# ders1.net
KiCad netlist of a schematic drawn in EAGLE
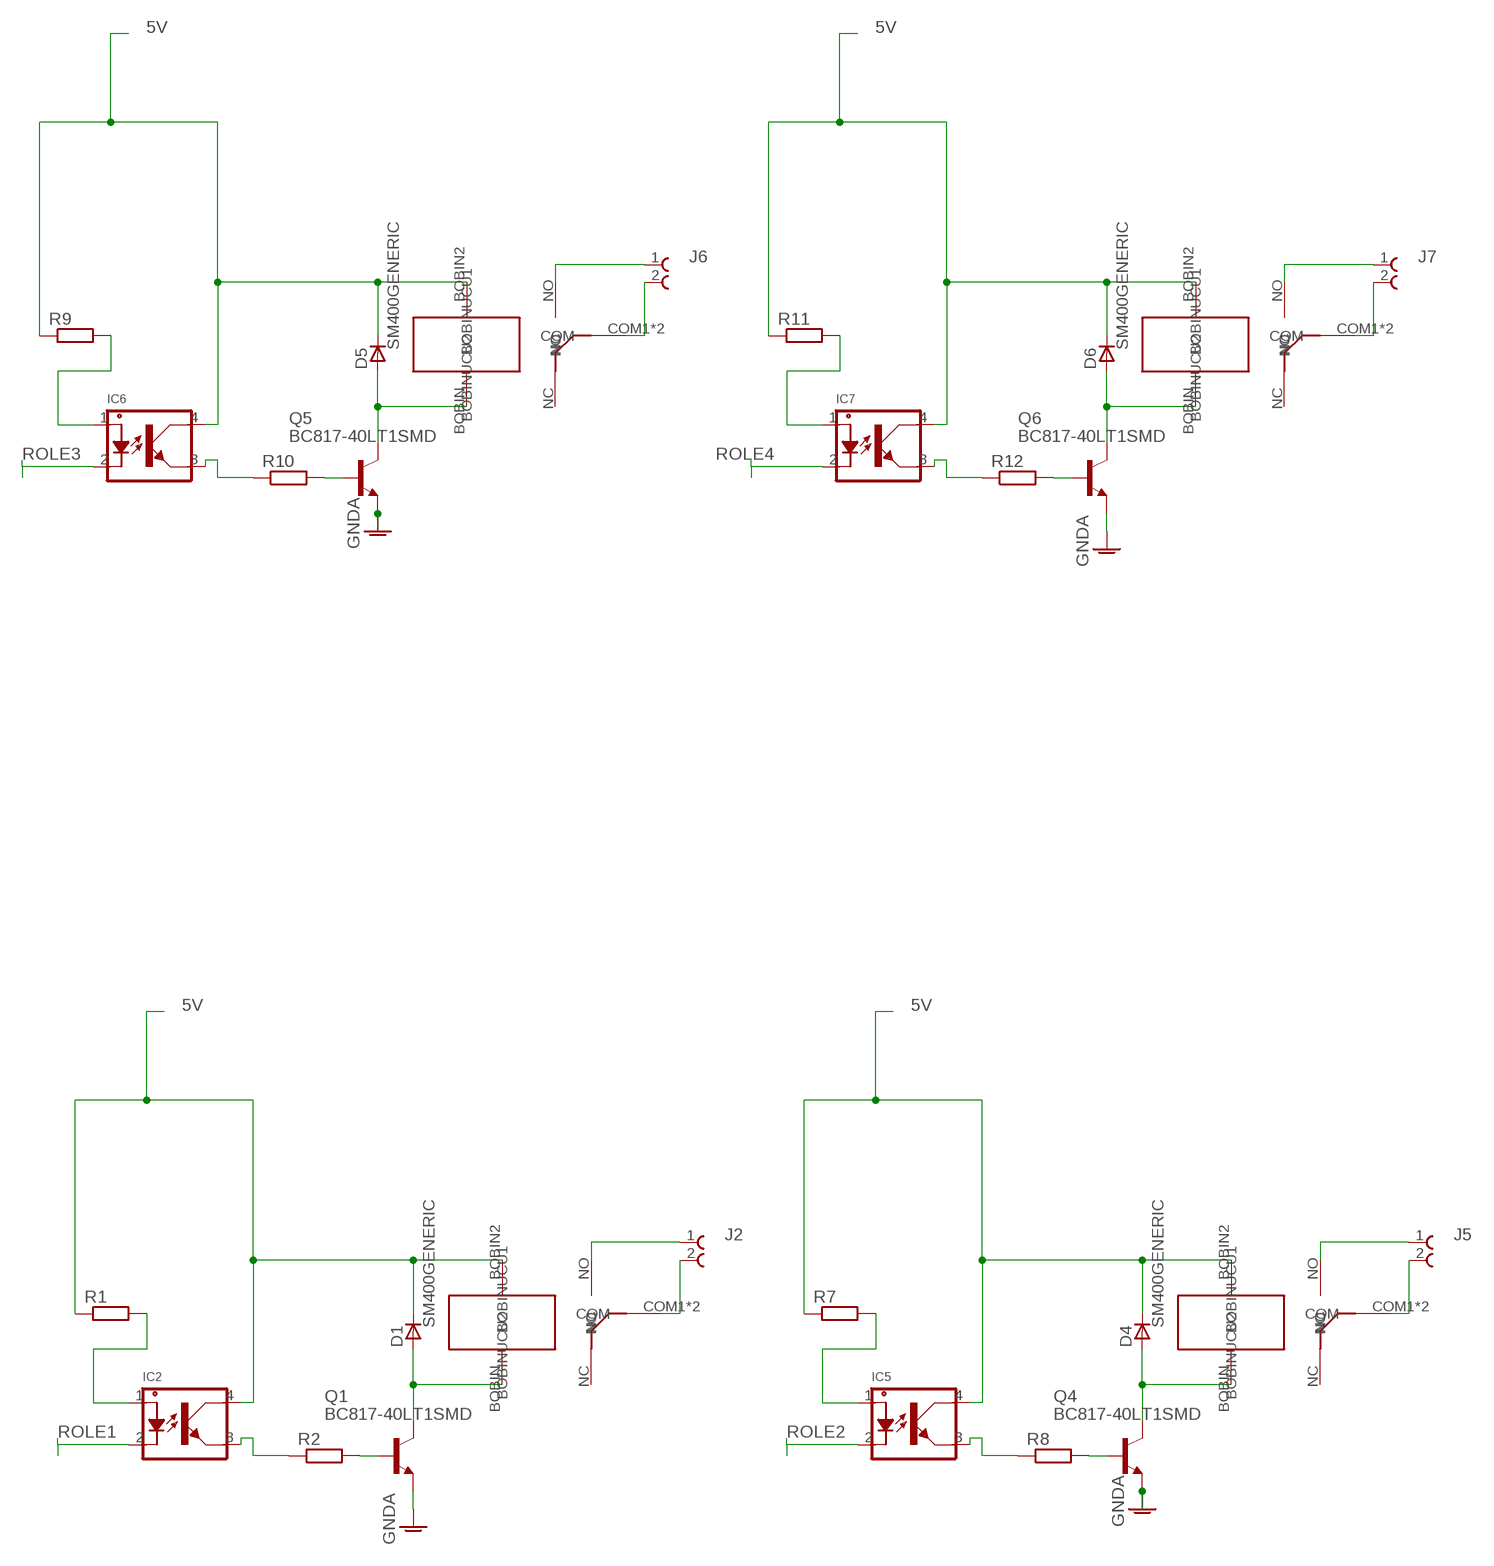
[diagram p0: schematic, sheet 1, part 1 of 2]
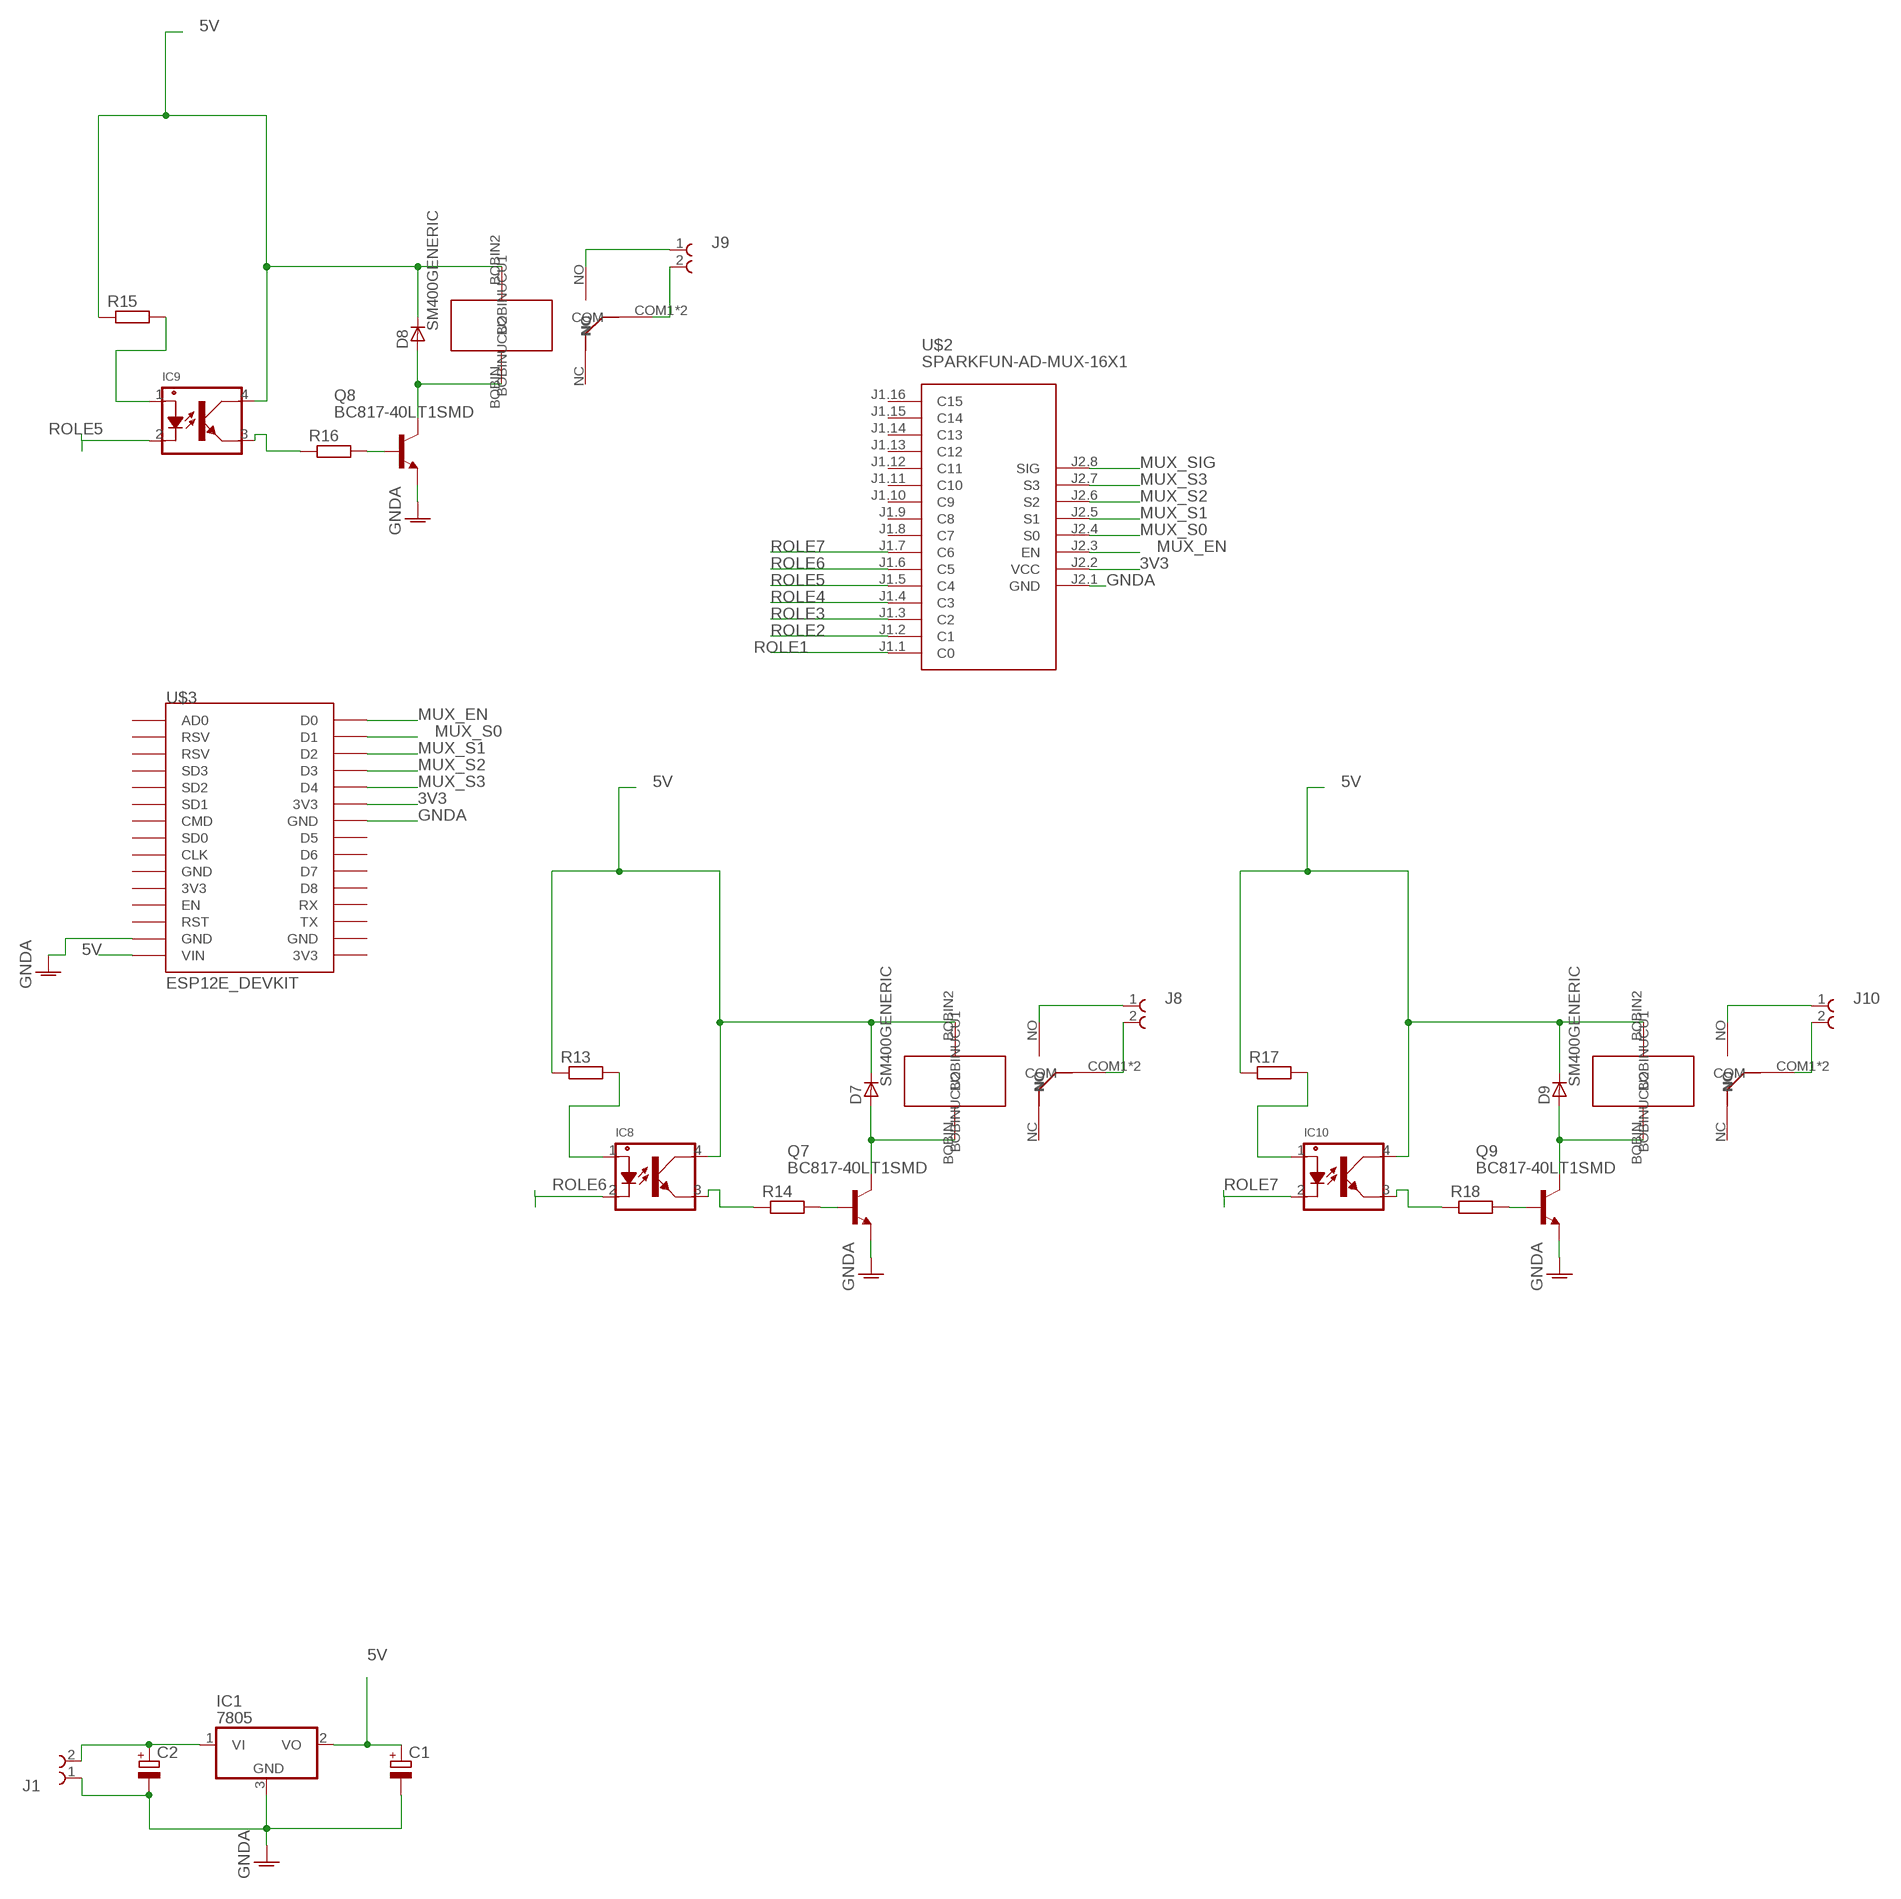
[diagram p1: schematic, sheet 1, part 2 of 2]

(export (version "E")
  (design (tool "Eeschema 10.0.6"))
  (components
    (comp (ref "C1")
      (value "CPOL-EU153CLV-0405")
      (footprint "eagle-import:153CLV-0405")
      (libsource (lib "eagle-import") (part "CPOL-EU153CLV-0405"))
    )
    (comp (ref "C2")
      (value "CPOL-EU153CLV-0405")
      (footprint "eagle-import:153CLV-0405")
      (libsource (lib "eagle-import") (part "CPOL-EU153CLV-0405"))
    )
    (comp (ref "D1")
      (value "SM400GENERIC")
      (footprint "eagle-import:MELF-MLL41_DO213AB")
      (libsource (lib "eagle-import") (part "SM400GENERIC"))
    )
    (comp (ref "D4")
      (value "SM400GENERIC")
      (footprint "eagle-import:MELF-MLL41_DO213AB")
      (libsource (lib "eagle-import") (part "SM400GENERIC"))
    )
    (comp (ref "D5")
      (value "SM400GENERIC")
      (footprint "eagle-import:MELF-MLL41_DO213AB")
      (libsource (lib "eagle-import") (part "SM400GENERIC"))
    )
    (comp (ref "D6")
      (value "SM400GENERIC")
      (footprint "eagle-import:MELF-MLL41_DO213AB")
      (libsource (lib "eagle-import") (part "SM400GENERIC"))
    )
    (comp (ref "D7")
      (value "SM400GENERIC")
      (footprint "eagle-import:MELF-MLL41_DO213AB")
      (libsource (lib "eagle-import") (part "SM400GENERIC"))
    )
    (comp (ref "D8")
      (value "SM400GENERIC")
      (footprint "eagle-import:MELF-MLL41_DO213AB")
      (libsource (lib "eagle-import") (part "SM400GENERIC"))
    )
    (comp (ref "D9")
      (value "SM400GENERIC")
      (footprint "eagle-import:MELF-MLL41_DO213AB")
      (libsource (lib "eagle-import") (part "SM400GENERIC"))
    )
    (comp (ref "IC1")
      (value "7805")
      (footprint "eagle-import:TO252")
      (libsource (lib "eagle-import") (part "7805"))
    )
    (comp (ref "IC2")
      (value "LTV-817SMD")
      (footprint "eagle-import:SMD-4")
      (fields (field (name "MF") "Lite-On Inc.") (field (name "MP") "LTV-817"))
      (libsource (lib "eagle-import") (part "LTV-817SMD"))
    )
    (comp (ref "IC5")
      (value "LTV-817SMD")
      (footprint "eagle-import:SMD-4")
      (fields (field (name "MF") "Lite-On Inc.") (field (name "MP") "LTV-817"))
      (libsource (lib "eagle-import") (part "LTV-817SMD"))
    )
    (comp (ref "IC6")
      (value "LTV-817SMD")
      (footprint "eagle-import:SMD-4")
      (fields (field (name "MF") "Lite-On Inc.") (field (name "MP") "LTV-817"))
      (libsource (lib "eagle-import") (part "LTV-817SMD"))
    )
    (comp (ref "IC7")
      (value "LTV-817SMD")
      (footprint "eagle-import:SMD-4")
      (fields (field (name "MF") "Lite-On Inc.") (field (name "MP") "LTV-817"))
      (libsource (lib "eagle-import") (part "LTV-817SMD"))
    )
    (comp (ref "IC8")
      (value "LTV-817SMD")
      (footprint "eagle-import:SMD-4")
      (fields (field (name "MF") "Lite-On Inc.") (field (name "MP") "LTV-817"))
      (libsource (lib "eagle-import") (part "LTV-817SMD"))
    )
    (comp (ref "IC9")
      (value "LTV-817SMD")
      (footprint "eagle-import:SMD-4")
      (fields (field (name "MF") "Lite-On Inc.") (field (name "MP") "LTV-817"))
      (libsource (lib "eagle-import") (part "LTV-817SMD"))
    )
    (comp (ref "IC10")
      (value "LTV-817SMD")
      (footprint "eagle-import:SMD-4")
      (fields (field (name "MF") "Lite-On Inc.") (field (name "MP") "LTV-817"))
      (libsource (lib "eagle-import") (part "LTV-817SMD"))
    )
    (comp (ref "J1")
      (value "691701540002B")
      (footprint "eagle-import:691701540002B")
      (libsource (lib "eagle-import") (part "691701540002B"))
    )
    (comp (ref "J2")
      (value "691701540002B")
      (footprint "eagle-import:691701540002B")
      (libsource (lib "eagle-import") (part "691701540002B"))
    )
    (comp (ref "J5")
      (value "691701540002B")
      (footprint "eagle-import:691701540002B")
      (libsource (lib "eagle-import") (part "691701540002B"))
    )
    (comp (ref "J6")
      (value "691701540002B")
      (footprint "eagle-import:691701540002B")
      (libsource (lib "eagle-import") (part "691701540002B"))
    )
    (comp (ref "J7")
      (value "691701540002B")
      (footprint "eagle-import:691701540002B")
      (libsource (lib "eagle-import") (part "691701540002B"))
    )
    (comp (ref "J8")
      (value "691701540002B")
      (footprint "eagle-import:691701540002B")
      (libsource (lib "eagle-import") (part "691701540002B"))
    )
    (comp (ref "J9")
      (value "691701540002B")
      (footprint "eagle-import:691701540002B")
      (libsource (lib "eagle-import") (part "691701540002B"))
    )
    (comp (ref "J10")
      (value "691701540002B")
      (footprint "eagle-import:691701540002B")
      (libsource (lib "eagle-import") (part "691701540002B"))
    )
    (comp (ref "Q1")
      (value "BC817-40LT1SMD")
      (footprint "eagle-import:SOT23-BEC")
      (libsource (lib "eagle-import") (part "BC817SMD-40LT1"))
    )
    (comp (ref "Q4")
      (value "BC817-40LT1SMD")
      (footprint "eagle-import:SOT23-BEC")
      (libsource (lib "eagle-import") (part "BC817SMD-40LT1"))
    )
    (comp (ref "Q5")
      (value "BC817-40LT1SMD")
      (footprint "eagle-import:SOT23-BEC")
      (libsource (lib "eagle-import") (part "BC817SMD-40LT1"))
    )
    (comp (ref "Q6")
      (value "BC817-40LT1SMD")
      (footprint "eagle-import:SOT23-BEC")
      (libsource (lib "eagle-import") (part "BC817SMD-40LT1"))
    )
    (comp (ref "Q7")
      (value "BC817-40LT1SMD")
      (footprint "eagle-import:SOT23-BEC")
      (libsource (lib "eagle-import") (part "BC817SMD-40LT1"))
    )
    (comp (ref "Q8")
      (value "BC817-40LT1SMD")
      (footprint "eagle-import:SOT23-BEC")
      (libsource (lib "eagle-import") (part "BC817SMD-40LT1"))
    )
    (comp (ref "Q9")
      (value "BC817-40LT1SMD")
      (footprint "eagle-import:SOT23-BEC")
      (libsource (lib "eagle-import") (part "BC817SMD-40LT1"))
    )
    (comp (ref "R1")
      (value "R-EU_R1206")
      (footprint "eagle-import:R1206")
      (libsource (lib "eagle-import") (part "R-EU_R1206"))
    )
    (comp (ref "R2")
      (value "R-EU_R1206")
      (footprint "eagle-import:R1206")
      (libsource (lib "eagle-import") (part "R-EU_R1206"))
    )
    (comp (ref "R7")
      (value "R-EU_R1206")
      (footprint "eagle-import:R1206")
      (libsource (lib "eagle-import") (part "R-EU_R1206"))
    )
    (comp (ref "R8")
      (value "R-EU_R1206")
      (footprint "eagle-import:R1206")
      (libsource (lib "eagle-import") (part "R-EU_R1206"))
    )
    (comp (ref "R9")
      (value "R-EU_R1206")
      (footprint "eagle-import:R1206")
      (libsource (lib "eagle-import") (part "R-EU_R1206"))
    )
    (comp (ref "R10")
      (value "R-EU_R1206")
      (footprint "eagle-import:R1206")
      (libsource (lib "eagle-import") (part "R-EU_R1206"))
    )
    (comp (ref "R11")
      (value "R-EU_R1206")
      (footprint "eagle-import:R1206")
      (libsource (lib "eagle-import") (part "R-EU_R1206"))
    )
    (comp (ref "R12")
      (value "R-EU_R1206")
      (footprint "eagle-import:R1206")
      (libsource (lib "eagle-import") (part "R-EU_R1206"))
    )
    (comp (ref "R13")
      (value "R-EU_R1206")
      (footprint "eagle-import:R1206")
      (libsource (lib "eagle-import") (part "R-EU_R1206"))
    )
    (comp (ref "R14")
      (value "R-EU_R1206")
      (footprint "eagle-import:R1206")
      (libsource (lib "eagle-import") (part "R-EU_R1206"))
    )
    (comp (ref "R15")
      (value "R-EU_R1206")
      (footprint "eagle-import:R1206")
      (libsource (lib "eagle-import") (part "R-EU_R1206"))
    )
    (comp (ref "R16")
      (value "R-EU_R1206")
      (footprint "eagle-import:R1206")
      (libsource (lib "eagle-import") (part "R-EU_R1206"))
    )
    (comp (ref "R17")
      (value "R-EU_R1206")
      (footprint "eagle-import:R1206")
      (libsource (lib "eagle-import") (part "R-EU_R1206"))
    )
    (comp (ref "R18")
      (value "R-EU_R1206")
      (footprint "eagle-import:R1206")
      (libsource (lib "eagle-import") (part "R-EU_R1206"))
    )
    (comp (ref "U$1")
      (value "HK23F-DC5V-SHG")
      (footprint "eagle-import:HK23F")
      (libsource (lib "eagle-import") (part "HK23F-DC5V-SHG"))
    )
    (comp (ref "U$2")
      (value "SPARKFUN-AD-MUX-16X1")
      (footprint "eagle-import:SPARKFUN-AD-MUX-16X1")
      (libsource (lib "eagle-import") (part "SPARKFUN-AD-MUX-16X1"))
    )
    (comp (ref "U$3")
      (value "ESP12E_DEVKIT")
      (footprint "eagle-import:ESP12E_DEVKIT")
      (libsource (lib "eagle-import") (part "ESP12E_DEVKIT"))
    )
    (comp (ref "U$4")
      (value "HK23F-DC5V-SHG")
      (footprint "eagle-import:HK23F")
      (libsource (lib "eagle-import") (part "HK23F-DC5V-SHG"))
    )
    (comp (ref "U$5")
      (value "HK23F-DC5V-SHG")
      (footprint "eagle-import:HK23F")
      (libsource (lib "eagle-import") (part "HK23F-DC5V-SHG"))
    )
    (comp (ref "U$6")
      (value "HK23F-DC5V-SHG")
      (footprint "eagle-import:HK23F")
      (libsource (lib "eagle-import") (part "HK23F-DC5V-SHG"))
    )
    (comp (ref "U$7")
      (value "HK23F-DC5V-SHG")
      (footprint "eagle-import:HK23F")
      (libsource (lib "eagle-import") (part "HK23F-DC5V-SHG"))
    )
    (comp (ref "U$8")
      (value "HK23F-DC5V-SHG")
      (footprint "eagle-import:HK23F")
      (libsource (lib "eagle-import") (part "HK23F-DC5V-SHG"))
    )
    (comp (ref "U$9")
      (value "HK23F-DC5V-SHG")
      (footprint "eagle-import:HK23F")
      (libsource (lib "eagle-import") (part "HK23F-DC5V-SHG"))
    )
  )
  (nets
    (net (code "1") (name "/3V3") (class "Default")
      (node (ref "U$2") (pin "J2.2") (pinfunction "VCC_J2.2") (pintype "power_in"))
      (node (ref "U$3") (pin "3V3@1") (pinfunction "3V3_3V3@1") (pintype "bidirectional"))
    )
    (net (code "2") (name "/5V") (class "Default")
      (node (ref "C1") (pin "+") (pinfunction "+_+") (pintype "passive"))
      (node (ref "D1") (pin "C") (pinfunction "C_C") (pintype "passive"))
      (node (ref "D4") (pin "C") (pinfunction "C_C") (pintype "passive"))
      (node (ref "D5") (pin "C") (pinfunction "C_C") (pintype "passive"))
      (node (ref "D6") (pin "C") (pinfunction "C_C") (pintype "passive"))
      (node (ref "D7") (pin "C") (pinfunction "C_C") (pintype "passive"))
      (node (ref "D8") (pin "C") (pinfunction "C_C") (pintype "passive"))
      (node (ref "D9") (pin "C") (pinfunction "C_C") (pintype "passive"))
      (node (ref "IC1") (pin "2") (pinfunction "VO_2") (pintype "passive"))
      (node (ref "IC10") (pin "4") (pinfunction "4_4") (pintype "input"))
      (node (ref "IC2") (pin "4") (pinfunction "4_4") (pintype "input"))
      (node (ref "IC5") (pin "4") (pinfunction "4_4") (pintype "input"))
      (node (ref "IC6") (pin "4") (pinfunction "4_4") (pintype "input"))
      (node (ref "IC7") (pin "4") (pinfunction "4_4") (pintype "input"))
      (node (ref "IC8") (pin "4") (pinfunction "4_4") (pintype "input"))
      (node (ref "IC9") (pin "4") (pinfunction "4_4") (pintype "input"))
      (node (ref "R1") (pin "1") (pinfunction "1_1") (pintype "passive"))
      (node (ref "R11") (pin "1") (pinfunction "1_1") (pintype "passive"))
      (node (ref "R13") (pin "1") (pinfunction "1_1") (pintype "passive"))
      (node (ref "R15") (pin "1") (pinfunction "1_1") (pintype "passive"))
      (node (ref "R17") (pin "1") (pinfunction "1_1") (pintype "passive"))
      (node (ref "R7") (pin "1") (pinfunction "1_1") (pintype "passive"))
      (node (ref "R9") (pin "1") (pinfunction "1_1") (pintype "passive"))
      (node (ref "U$1") (pin "BOBIN2") (pinfunction "BOBINUCU2_BOBIN2") (pintype "bidirectional"))
      (node (ref "U$3") (pin "VIN") (pinfunction "VIN_VIN") (pintype "bidirectional"))
      (node (ref "U$4") (pin "BOBIN2") (pinfunction "BOBINUCU2_BOBIN2") (pintype "bidirectional"))
      (node (ref "U$5") (pin "BOBIN2") (pinfunction "BOBINUCU2_BOBIN2") (pintype "bidirectional"))
      (node (ref "U$6") (pin "BOBIN2") (pinfunction "BOBINUCU2_BOBIN2") (pintype "bidirectional"))
      (node (ref "U$7") (pin "BOBIN2") (pinfunction "BOBINUCU2_BOBIN2") (pintype "bidirectional"))
      (node (ref "U$8") (pin "BOBIN2") (pinfunction "BOBINUCU2_BOBIN2") (pintype "bidirectional"))
      (node (ref "U$9") (pin "BOBIN2") (pinfunction "BOBINUCU2_BOBIN2") (pintype "bidirectional"))
    )
    (net (code "3") (name "/MUX_EN") (class "Default")
      (node (ref "U$2") (pin "J2.3") (pinfunction "EN_J2.3") (pintype "input"))
      (node (ref "U$3") (pin "D0") (pinfunction "D0_D0") (pintype "bidirectional"))
    )
    (net (code "4") (name "/MUX_S0") (class "Default")
      (node (ref "U$2") (pin "J2.4") (pinfunction "S0_J2.4") (pintype "bidirectional"))
      (node (ref "U$3") (pin "D1") (pinfunction "D1_D1") (pintype "bidirectional"))
    )
    (net (code "5") (name "/MUX_S1") (class "Default")
      (node (ref "U$2") (pin "J2.5") (pinfunction "S1_J2.5") (pintype "bidirectional"))
      (node (ref "U$3") (pin "D2") (pinfunction "D2_D2") (pintype "bidirectional"))
    )
    (net (code "6") (name "/MUX_S2") (class "Default")
      (node (ref "U$2") (pin "J2.6") (pinfunction "S2_J2.6") (pintype "bidirectional"))
      (node (ref "U$3") (pin "D3") (pinfunction "D3_D3") (pintype "bidirectional"))
    )
    (net (code "7") (name "/MUX_S3") (class "Default")
      (node (ref "U$2") (pin "J2.7") (pinfunction "S3_J2.7") (pintype "bidirectional"))
      (node (ref "U$3") (pin "D4") (pinfunction "D4_D4") (pintype "bidirectional"))
    )
    (net (code "8") (name "/MUX_SIG") (class "Default")
      (node (ref "U$2") (pin "J2.8") (pinfunction "SIG_J2.8") (pintype "bidirectional"))
    )
    (net (code "9") (name "/ROLE1") (class "Default")
      (node (ref "IC2") (pin "2") (pinfunction "2_2") (pintype "output"))
      (node (ref "U$2") (pin "J1.1") (pinfunction "C0_J1.1") (pintype "bidirectional"))
    )
    (net (code "10") (name "/ROLE2") (class "Default")
      (node (ref "IC5") (pin "2") (pinfunction "2_2") (pintype "output"))
      (node (ref "U$2") (pin "J1.2") (pinfunction "C1_J1.2") (pintype "bidirectional"))
    )
    (net (code "11") (name "/ROLE3") (class "Default")
      (node (ref "IC6") (pin "2") (pinfunction "2_2") (pintype "output"))
      (node (ref "U$2") (pin "J1.3") (pinfunction "C2_J1.3") (pintype "bidirectional"))
    )
    (net (code "12") (name "/ROLE4") (class "Default")
      (node (ref "IC7") (pin "2") (pinfunction "2_2") (pintype "output"))
      (node (ref "U$2") (pin "J1.4") (pinfunction "C3_J1.4") (pintype "bidirectional"))
    )
    (net (code "13") (name "/ROLE5") (class "Default")
      (node (ref "IC9") (pin "2") (pinfunction "2_2") (pintype "output"))
      (node (ref "U$2") (pin "J1.5") (pinfunction "C4_J1.5") (pintype "bidirectional"))
    )
    (net (code "14") (name "/ROLE6") (class "Default")
      (node (ref "IC8") (pin "2") (pinfunction "2_2") (pintype "output"))
      (node (ref "U$2") (pin "J1.6") (pinfunction "C5_J1.6") (pintype "bidirectional"))
    )
    (net (code "15") (name "/ROLE7") (class "Default")
      (node (ref "IC10") (pin "2") (pinfunction "2_2") (pintype "output"))
      (node (ref "U$2") (pin "J1.7") (pinfunction "C6_J1.7") (pintype "bidirectional"))
    )
    (net (code "16") (name "GNDA") (class "Default")
      (node (ref "C1") (pin "-") (pinfunction "-_-") (pintype "passive"))
      (node (ref "C2") (pin "-") (pinfunction "-_-") (pintype "passive"))
      (node (ref "IC1") (pin "3") (pinfunction "GND_3") (pintype "passive"))
      (node (ref "J1") (pin "1") (pinfunction "1_1") (pintype "passive"))
      (node (ref "Q1") (pin "E") (pinfunction "E_E") (pintype "passive"))
      (node (ref "Q4") (pin "E") (pinfunction "E_E") (pintype "passive"))
      (node (ref "Q5") (pin "E") (pinfunction "E_E") (pintype "passive"))
      (node (ref "Q6") (pin "E") (pinfunction "E_E") (pintype "passive"))
      (node (ref "Q7") (pin "E") (pinfunction "E_E") (pintype "passive"))
      (node (ref "Q8") (pin "E") (pinfunction "E_E") (pintype "passive"))
      (node (ref "Q9") (pin "E") (pinfunction "E_E") (pintype "passive"))
      (node (ref "U$2") (pin "J2.1") (pinfunction "GND_J2.1") (pintype "power_in"))
      (node (ref "U$3") (pin "GND@1") (pinfunction "GND_GND@1") (pintype "bidirectional"))
      (node (ref "U$3") (pin "GND@2") (pinfunction "GND_GND@2") (pintype "bidirectional"))
    )
    (net (code "17") (name "Net-(IC1-VI)") (class "Default")
      (node (ref "C2") (pin "+") (pinfunction "+_+") (pintype "passive"))
      (node (ref "IC1") (pin "1") (pinfunction "VI_1") (pintype "input"))
      (node (ref "J1") (pin "2") (pinfunction "2_2") (pintype "passive"))
    )
    (net (code "18") (name "Net-(IC2-Pad1)") (class "Default")
      (node (ref "IC2") (pin "1") (pinfunction "1_1") (pintype "input"))
      (node (ref "R1") (pin "2") (pinfunction "2_2") (pintype "passive"))
    )
    (net (code "19") (name "Net-(IC2-Pad3)") (class "Default")
      (node (ref "IC2") (pin "3") (pinfunction "3_3") (pintype "output"))
      (node (ref "R2") (pin "1") (pinfunction "1_1") (pintype "passive"))
    )
    (net (code "20") (name "Net-(IC5-Pad1)") (class "Default")
      (node (ref "IC5") (pin "1") (pinfunction "1_1") (pintype "input"))
      (node (ref "R7") (pin "2") (pinfunction "2_2") (pintype "passive"))
    )
    (net (code "21") (name "Net-(IC5-Pad3)") (class "Default")
      (node (ref "IC5") (pin "3") (pinfunction "3_3") (pintype "output"))
      (node (ref "R8") (pin "1") (pinfunction "1_1") (pintype "passive"))
    )
    (net (code "22") (name "Net-(IC6-Pad1)") (class "Default")
      (node (ref "IC6") (pin "1") (pinfunction "1_1") (pintype "input"))
      (node (ref "R9") (pin "2") (pinfunction "2_2") (pintype "passive"))
    )
    (net (code "23") (name "Net-(IC6-Pad3)") (class "Default")
      (node (ref "IC6") (pin "3") (pinfunction "3_3") (pintype "output"))
      (node (ref "R10") (pin "1") (pinfunction "1_1") (pintype "passive"))
    )
    (net (code "24") (name "Net-(IC7-Pad1)") (class "Default")
      (node (ref "IC7") (pin "1") (pinfunction "1_1") (pintype "input"))
      (node (ref "R11") (pin "2") (pinfunction "2_2") (pintype "passive"))
    )
    (net (code "25") (name "Net-(IC7-Pad3)") (class "Default")
      (node (ref "IC7") (pin "3") (pinfunction "3_3") (pintype "output"))
      (node (ref "R12") (pin "1") (pinfunction "1_1") (pintype "passive"))
    )
    (net (code "26") (name "Net-(IC8-Pad1)") (class "Default")
      (node (ref "IC8") (pin "1") (pinfunction "1_1") (pintype "input"))
      (node (ref "R13") (pin "2") (pinfunction "2_2") (pintype "passive"))
    )
    (net (code "27") (name "Net-(IC8-Pad3)") (class "Default")
      (node (ref "IC8") (pin "3") (pinfunction "3_3") (pintype "output"))
      (node (ref "R14") (pin "1") (pinfunction "1_1") (pintype "passive"))
    )
    (net (code "28") (name "Net-(IC9-Pad1)") (class "Default")
      (node (ref "IC9") (pin "1") (pinfunction "1_1") (pintype "input"))
      (node (ref "R15") (pin "2") (pinfunction "2_2") (pintype "passive"))
    )
    (net (code "29") (name "Net-(IC9-Pad3)") (class "Default")
      (node (ref "IC9") (pin "3") (pinfunction "3_3") (pintype "output"))
      (node (ref "R16") (pin "1") (pinfunction "1_1") (pintype "passive"))
    )
    (net (code "30") (name "Net-(IC10-Pad1)") (class "Default")
      (node (ref "IC10") (pin "1") (pinfunction "1_1") (pintype "input"))
      (node (ref "R17") (pin "2") (pinfunction "2_2") (pintype "passive"))
    )
    (net (code "31") (name "Net-(IC10-Pad3)") (class "Default")
      (node (ref "IC10") (pin "3") (pinfunction "3_3") (pintype "output"))
      (node (ref "R18") (pin "1") (pinfunction "1_1") (pintype "passive"))
    )
    (net (code "32") (name "Net-(J2-Pad1)") (class "Default")
      (node (ref "J2") (pin "1") (pinfunction "1_1") (pintype "passive"))
      (node (ref "U$1") (pin "NO") (pinfunction "NO_NO") (pintype "bidirectional"))
    )
    (net (code "33") (name "Net-(J2-Pad2)") (class "Default")
      (node (ref "J2") (pin "2") (pinfunction "2_2") (pintype "passive"))
      (node (ref "U$1") (pin "COM1") (pinfunction "COM_COM1") (pintype "bidirectional"))
      (node (ref "U$1") (pin "COM2") (pinfunction "COM_COM2") (pintype "bidirectional"))
    )
    (net (code "34") (name "Net-(J5-Pad1)") (class "Default")
      (node (ref "J5") (pin "1") (pinfunction "1_1") (pintype "passive"))
      (node (ref "U$4") (pin "NO") (pinfunction "NO_NO") (pintype "bidirectional"))
    )
    (net (code "35") (name "Net-(J5-Pad2)") (class "Default")
      (node (ref "J5") (pin "2") (pinfunction "2_2") (pintype "passive"))
      (node (ref "U$4") (pin "COM1") (pinfunction "COM_COM1") (pintype "bidirectional"))
      (node (ref "U$4") (pin "COM2") (pinfunction "COM_COM2") (pintype "bidirectional"))
    )
    (net (code "36") (name "Net-(J6-Pad1)") (class "Default")
      (node (ref "J6") (pin "1") (pinfunction "1_1") (pintype "passive"))
      (node (ref "U$5") (pin "NO") (pinfunction "NO_NO") (pintype "bidirectional"))
    )
    (net (code "37") (name "Net-(J6-Pad2)") (class "Default")
      (node (ref "J6") (pin "2") (pinfunction "2_2") (pintype "passive"))
      (node (ref "U$5") (pin "COM1") (pinfunction "COM_COM1") (pintype "bidirectional"))
      (node (ref "U$5") (pin "COM2") (pinfunction "COM_COM2") (pintype "bidirectional"))
    )
    (net (code "38") (name "Net-(J7-Pad1)") (class "Default")
      (node (ref "J7") (pin "1") (pinfunction "1_1") (pintype "passive"))
      (node (ref "U$6") (pin "NO") (pinfunction "NO_NO") (pintype "bidirectional"))
    )
    (net (code "39") (name "Net-(J7-Pad2)") (class "Default")
      (node (ref "J7") (pin "2") (pinfunction "2_2") (pintype "passive"))
      (node (ref "U$6") (pin "COM1") (pinfunction "COM_COM1") (pintype "bidirectional"))
      (node (ref "U$6") (pin "COM2") (pinfunction "COM_COM2") (pintype "bidirectional"))
    )
    (net (code "40") (name "Net-(J8-Pad1)") (class "Default")
      (node (ref "J8") (pin "1") (pinfunction "1_1") (pintype "passive"))
      (node (ref "U$7") (pin "NO") (pinfunction "NO_NO") (pintype "bidirectional"))
    )
    (net (code "41") (name "Net-(J8-Pad2)") (class "Default")
      (node (ref "J8") (pin "2") (pinfunction "2_2") (pintype "passive"))
      (node (ref "U$7") (pin "COM1") (pinfunction "COM_COM1") (pintype "bidirectional"))
      (node (ref "U$7") (pin "COM2") (pinfunction "COM_COM2") (pintype "bidirectional"))
    )
    (net (code "42") (name "Net-(J9-Pad1)") (class "Default")
      (node (ref "J9") (pin "1") (pinfunction "1_1") (pintype "passive"))
      (node (ref "U$8") (pin "NO") (pinfunction "NO_NO") (pintype "bidirectional"))
    )
    (net (code "43") (name "Net-(J9-Pad2)") (class "Default")
      (node (ref "J9") (pin "2") (pinfunction "2_2") (pintype "passive"))
      (node (ref "U$8") (pin "COM1") (pinfunction "COM_COM1") (pintype "bidirectional"))
      (node (ref "U$8") (pin "COM2") (pinfunction "COM_COM2") (pintype "bidirectional"))
    )
    (net (code "44") (name "Net-(J10-Pad1)") (class "Default")
      (node (ref "J10") (pin "1") (pinfunction "1_1") (pintype "passive"))
      (node (ref "U$9") (pin "NO") (pinfunction "NO_NO") (pintype "bidirectional"))
    )
    (net (code "45") (name "Net-(J10-Pad2)") (class "Default")
      (node (ref "J10") (pin "2") (pinfunction "2_2") (pintype "passive"))
      (node (ref "U$9") (pin "COM1") (pinfunction "COM_COM1") (pintype "bidirectional"))
      (node (ref "U$9") (pin "COM2") (pinfunction "COM_COM2") (pintype "bidirectional"))
    )
    (net (code "46") (name "Net-(Q1-PadB)") (class "Default")
      (node (ref "Q1") (pin "B") (pinfunction "B_B") (pintype "passive"))
      (node (ref "R2") (pin "2") (pinfunction "2_2") (pintype "passive"))
    )
    (net (code "47") (name "Net-(Q4-PadB)") (class "Default")
      (node (ref "Q4") (pin "B") (pinfunction "B_B") (pintype "passive"))
      (node (ref "R8") (pin "2") (pinfunction "2_2") (pintype "passive"))
    )
    (net (code "48") (name "Net-(Q5-PadB)") (class "Default")
      (node (ref "Q5") (pin "B") (pinfunction "B_B") (pintype "passive"))
      (node (ref "R10") (pin "2") (pinfunction "2_2") (pintype "passive"))
    )
    (net (code "49") (name "Net-(Q6-PadB)") (class "Default")
      (node (ref "Q6") (pin "B") (pinfunction "B_B") (pintype "passive"))
      (node (ref "R12") (pin "2") (pinfunction "2_2") (pintype "passive"))
    )
    (net (code "50") (name "Net-(Q7-PadB)") (class "Default")
      (node (ref "Q7") (pin "B") (pinfunction "B_B") (pintype "passive"))
      (node (ref "R14") (pin "2") (pinfunction "2_2") (pintype "passive"))
    )
    (net (code "51") (name "Net-(Q8-PadB)") (class "Default")
      (node (ref "Q8") (pin "B") (pinfunction "B_B") (pintype "passive"))
      (node (ref "R16") (pin "2") (pinfunction "2_2") (pintype "passive"))
    )
    (net (code "52") (name "Net-(Q9-PadB)") (class "Default")
      (node (ref "Q9") (pin "B") (pinfunction "B_B") (pintype "passive"))
      (node (ref "R18") (pin "2") (pinfunction "2_2") (pintype "passive"))
    )
    (net (code "53") (name "Net-(U$1-BOBINUCU1)") (class "Default")
      (node (ref "D1") (pin "A") (pinfunction "A_A") (pintype "passive"))
      (node (ref "Q1") (pin "C") (pinfunction "C_C") (pintype "passive"))
      (node (ref "U$1") (pin "BOBIN") (pinfunction "BOBINUCU1_BOBIN") (pintype "bidirectional"))
    )
    (net (code "54") (name "Net-(U$4-BOBINUCU1)") (class "Default")
      (node (ref "D4") (pin "A") (pinfunction "A_A") (pintype "passive"))
      (node (ref "Q4") (pin "C") (pinfunction "C_C") (pintype "passive"))
      (node (ref "U$4") (pin "BOBIN") (pinfunction "BOBINUCU1_BOBIN") (pintype "bidirectional"))
    )
    (net (code "55") (name "Net-(U$5-BOBINUCU1)") (class "Default")
      (node (ref "D5") (pin "A") (pinfunction "A_A") (pintype "passive"))
      (node (ref "Q5") (pin "C") (pinfunction "C_C") (pintype "passive"))
      (node (ref "U$5") (pin "BOBIN") (pinfunction "BOBINUCU1_BOBIN") (pintype "bidirectional"))
    )
    (net (code "56") (name "Net-(U$6-BOBINUCU1)") (class "Default")
      (node (ref "D6") (pin "A") (pinfunction "A_A") (pintype "passive"))
      (node (ref "Q6") (pin "C") (pinfunction "C_C") (pintype "passive"))
      (node (ref "U$6") (pin "BOBIN") (pinfunction "BOBINUCU1_BOBIN") (pintype "bidirectional"))
    )
    (net (code "57") (name "Net-(U$7-BOBINUCU1)") (class "Default")
      (node (ref "D7") (pin "A") (pinfunction "A_A") (pintype "passive"))
      (node (ref "Q7") (pin "C") (pinfunction "C_C") (pintype "passive"))
      (node (ref "U$7") (pin "BOBIN") (pinfunction "BOBINUCU1_BOBIN") (pintype "bidirectional"))
    )
    (net (code "58") (name "Net-(U$8-BOBINUCU1)") (class "Default")
      (node (ref "D8") (pin "A") (pinfunction "A_A") (pintype "passive"))
      (node (ref "Q8") (pin "C") (pinfunction "C_C") (pintype "passive"))
      (node (ref "U$8") (pin "BOBIN") (pinfunction "BOBINUCU1_BOBIN") (pintype "bidirectional"))
    )
    (net (code "59") (name "Net-(U$9-BOBINUCU1)") (class "Default")
      (node (ref "D9") (pin "A") (pinfunction "A_A") (pintype "passive"))
      (node (ref "Q9") (pin "C") (pinfunction "C_C") (pintype "passive"))
      (node (ref "U$9") (pin "BOBIN") (pinfunction "BOBINUCU1_BOBIN") (pintype "bidirectional"))
    )
    (net (code "60") (name "unconnected-(U$1-PadNC)") (class "Default")
      (node (ref "U$1") (pin "NC") (pinfunction "NC_NC") (pintype "bidirectional"))
    )
    (net (code "61") (name "unconnected-(U$2-C7-PadJ1.8)") (class "Default")
      (node (ref "U$2") (pin "J1.8") (pinfunction "C7_J1.8") (pintype "bidirectional"))
    )
    (net (code "62") (name "unconnected-(U$2-C8-PadJ1.9)") (class "Default")
      (node (ref "U$2") (pin "J1.9") (pinfunction "C8_J1.9") (pintype "bidirectional"))
    )
    (net (code "63") (name "unconnected-(U$2-C9-PadJ1.10)") (class "Default")
      (node (ref "U$2") (pin "J1.10") (pinfunction "C9_J1.10") (pintype "bidirectional"))
    )
    (net (code "64") (name "unconnected-(U$2-C10-PadJ1.11)") (class "Default")
      (node (ref "U$2") (pin "J1.11") (pinfunction "C10_J1.11") (pintype "bidirectional"))
    )
    (net (code "65") (name "unconnected-(U$2-C11-PadJ1.12)") (class "Default")
      (node (ref "U$2") (pin "J1.12") (pinfunction "C11_J1.12") (pintype "bidirectional"))
    )
    (net (code "66") (name "unconnected-(U$2-C12-PadJ1.13)") (class "Default")
      (node (ref "U$2") (pin "J1.13") (pinfunction "C12_J1.13") (pintype "bidirectional"))
    )
    (net (code "67") (name "unconnected-(U$2-C13-PadJ1.14)") (class "Default")
      (node (ref "U$2") (pin "J1.14") (pinfunction "C13_J1.14") (pintype "bidirectional"))
    )
    (net (code "68") (name "unconnected-(U$2-C14-PadJ1.15)") (class "Default")
      (node (ref "U$2") (pin "J1.15") (pinfunction "C14_J1.15") (pintype "bidirectional"))
    )
    (net (code "69") (name "unconnected-(U$2-C15-PadJ1.16)") (class "Default")
      (node (ref "U$2") (pin "J1.16") (pinfunction "C15_J1.16") (pintype "bidirectional"))
    )
    (net (code "70") (name "unconnected-(U$3-3V3-Pad3V3@0)") (class "Default")
      (node (ref "U$3") (pin "3V3@0") (pinfunction "3V3_3V3@0") (pintype "bidirectional"))
    )
    (net (code "71") (name "unconnected-(U$3-3V3-Pad3V3@2)") (class "Default")
      (node (ref "U$3") (pin "3V3@2") (pinfunction "3V3_3V3@2") (pintype "bidirectional"))
    )
    (net (code "72") (name "unconnected-(U$3-GND-PadGND@0)") (class "Default")
      (node (ref "U$3") (pin "GND@0") (pinfunction "GND_GND@0") (pintype "bidirectional"))
    )
    (net (code "73") (name "unconnected-(U$3-GND-PadGND@3)") (class "Default")
      (node (ref "U$3") (pin "GND@3") (pinfunction "GND_GND@3") (pintype "bidirectional"))
    )
    (net (code "74") (name "unconnected-(U$3-PadAD0)") (class "Default")
      (node (ref "U$3") (pin "AD0") (pinfunction "AD0_AD0") (pintype "bidirectional"))
    )
    (net (code "75") (name "unconnected-(U$3-PadCLK)") (class "Default")
      (node (ref "U$3") (pin "CLK") (pinfunction "CLK_CLK") (pintype "bidirectional"))
    )
    (net (code "76") (name "unconnected-(U$3-PadCMD)") (class "Default")
      (node (ref "U$3") (pin "CMD") (pinfunction "CMD_CMD") (pintype "bidirectional"))
    )
    (net (code "77") (name "unconnected-(U$3-PadD5)") (class "Default")
      (node (ref "U$3") (pin "D5") (pinfunction "D5_D5") (pintype "bidirectional"))
    )
    (net (code "78") (name "unconnected-(U$3-PadD6)") (class "Default")
      (node (ref "U$3") (pin "D6") (pinfunction "D6_D6") (pintype "bidirectional"))
    )
    (net (code "79") (name "unconnected-(U$3-PadD7)") (class "Default")
      (node (ref "U$3") (pin "D7") (pinfunction "D7_D7") (pintype "bidirectional"))
    )
    (net (code "80") (name "unconnected-(U$3-PadD8)") (class "Default")
      (node (ref "U$3") (pin "D8") (pinfunction "D8_D8") (pintype "bidirectional"))
    )
    (net (code "81") (name "unconnected-(U$3-PadEN)") (class "Default")
      (node (ref "U$3") (pin "EN") (pinfunction "EN_EN") (pintype "bidirectional"))
    )
    (net (code "82") (name "unconnected-(U$3-PadRST)") (class "Default")
      (node (ref "U$3") (pin "RST") (pinfunction "RST_RST") (pintype "bidirectional"))
    )
    (net (code "83") (name "unconnected-(U$3-PadRX)") (class "Default")
      (node (ref "U$3") (pin "RX") (pinfunction "RX_RX") (pintype "bidirectional"))
    )
    (net (code "84") (name "unconnected-(U$3-PadSD0)") (class "Default")
      (node (ref "U$3") (pin "SD0") (pinfunction "SD0_SD0") (pintype "bidirectional"))
    )
    (net (code "85") (name "unconnected-(U$3-PadSD1)") (class "Default")
      (node (ref "U$3") (pin "SD1") (pinfunction "SD1_SD1") (pintype "bidirectional"))
    )
    (net (code "86") (name "unconnected-(U$3-PadSD2)") (class "Default")
      (node (ref "U$3") (pin "SD2") (pinfunction "SD2_SD2") (pintype "bidirectional"))
    )
    (net (code "87") (name "unconnected-(U$3-PadSD3)") (class "Default")
      (node (ref "U$3") (pin "SD3") (pinfunction "SD3_SD3") (pintype "bidirectional"))
    )
    (net (code "88") (name "unconnected-(U$3-PadTX)") (class "Default")
      (node (ref "U$3") (pin "TX") (pinfunction "TX_TX") (pintype "bidirectional"))
    )
    (net (code "89") (name "unconnected-(U$3-RSV-PadRSV@0)") (class "Default")
      (node (ref "U$3") (pin "RSV@0") (pinfunction "RSV_RSV@0") (pintype "bidirectional"))
    )
    (net (code "90") (name "unconnected-(U$3-RSV-PadRSV@1)") (class "Default")
      (node (ref "U$3") (pin "RSV@1") (pinfunction "RSV_RSV@1") (pintype "bidirectional"))
    )
    (net (code "91") (name "unconnected-(U$4-PadNC)") (class "Default")
      (node (ref "U$4") (pin "NC") (pinfunction "NC_NC") (pintype "bidirectional"))
    )
    (net (code "92") (name "unconnected-(U$5-PadNC)") (class "Default")
      (node (ref "U$5") (pin "NC") (pinfunction "NC_NC") (pintype "bidirectional"))
    )
    (net (code "93") (name "unconnected-(U$6-PadNC)") (class "Default")
      (node (ref "U$6") (pin "NC") (pinfunction "NC_NC") (pintype "bidirectional"))
    )
    (net (code "94") (name "unconnected-(U$7-PadNC)") (class "Default")
      (node (ref "U$7") (pin "NC") (pinfunction "NC_NC") (pintype "bidirectional"))
    )
    (net (code "95") (name "unconnected-(U$8-PadNC)") (class "Default")
      (node (ref "U$8") (pin "NC") (pinfunction "NC_NC") (pintype "bidirectional"))
    )
    (net (code "96") (name "unconnected-(U$9-PadNC)") (class "Default")
      (node (ref "U$9") (pin "NC") (pinfunction "NC_NC") (pintype "bidirectional"))
    )
  )
)
